# TEST_USB.net
KiCad netlist of a schematic drawn in Altium Designer
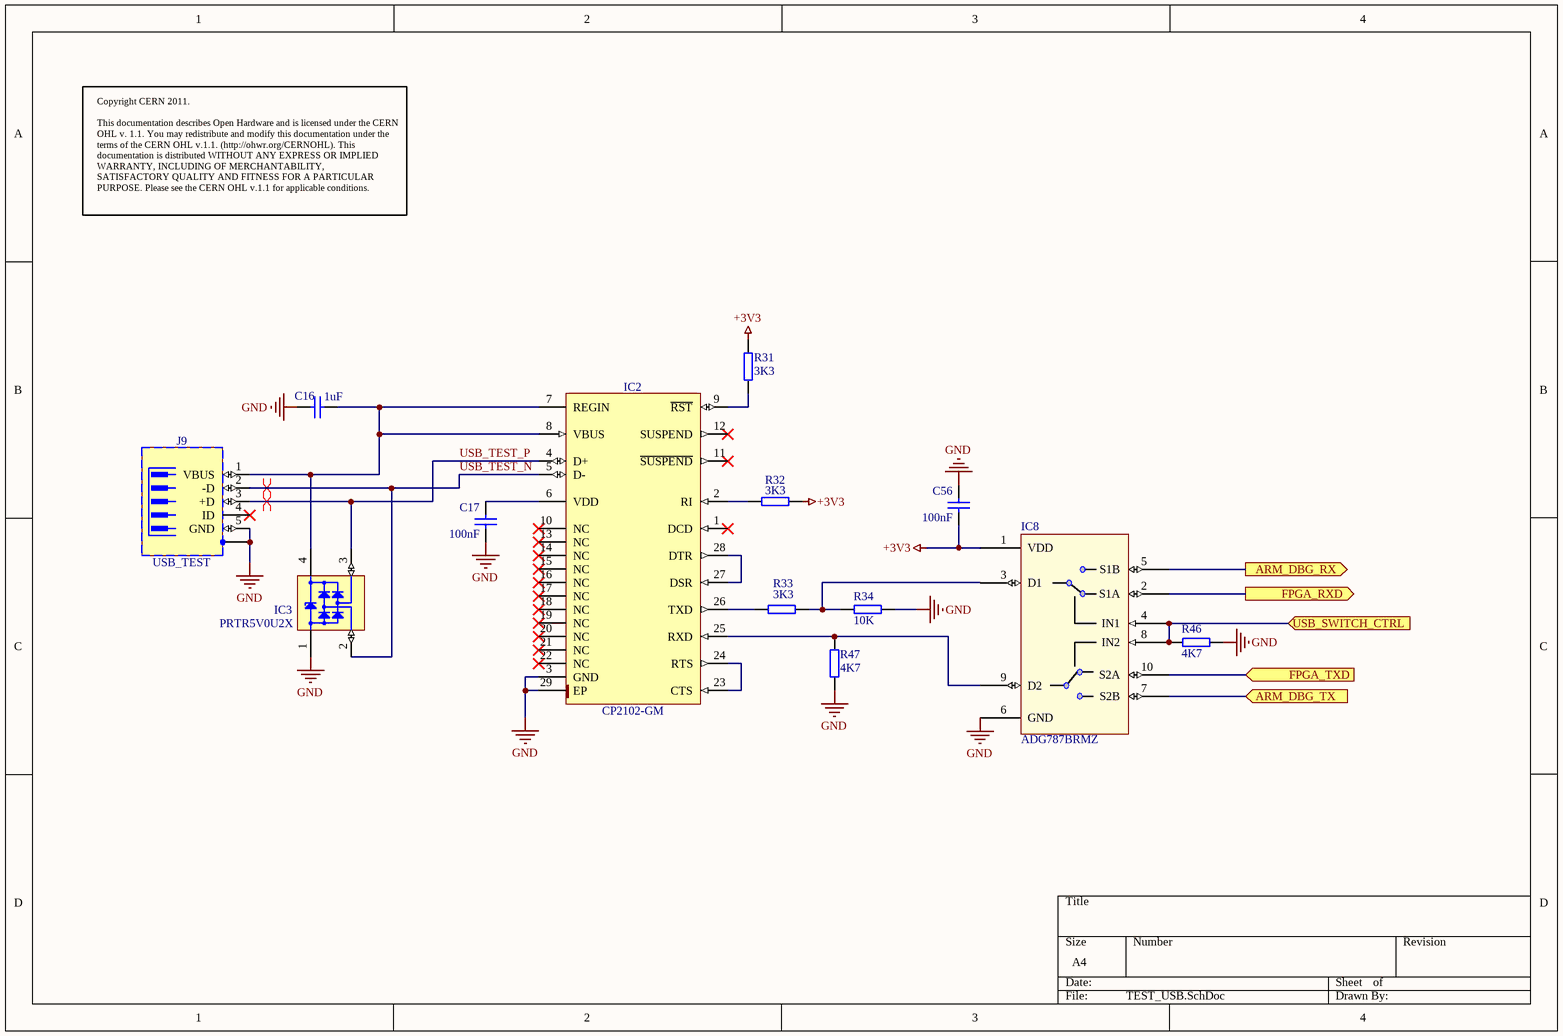
[diagram p0: TEST_USB.SchDoc]

(export (version "E")
  (design (tool "Eeschema 10.0.6"))
  (components
    (comp (ref "C16")
      (value "1uF")
      (footprint "CC1608-0603")
      (description "Capacitor")
      (fields
        (field (name "TOLERANCE") "±10%")
        (field (name "VOLTAGE") "25V")
        (field (name "PUBLISHER") "Altium Limited")
      )
      (libsource (lib "wr_switch") (part "Cap"))
    )
    (comp (ref "C17")
      (value "100nF")
      (footprint "CC1608-0603")
      (description "Capacitor")
      (fields
        (field (name "TOLERANCE") "±10%")
        (field (name "VOLTAGE") "16V")
        (field (name "PUBLISHER") "Altium Limited")
      )
      (libsource (lib "wr_switch") (part "Cap"))
    )
    (comp (ref "C56")
      (value "100nF")
      (footprint "CC1608-0603")
      (description "Capacitor")
      (fields
        (field (name "TOLERANCE") "±10%")
        (field (name "VOLTAGE") "16V")
        (field (name "PUBLISHER") "Altium Limited")
      )
      (libsource (lib "wr_switch") (part "Cap"))
    )
    (comp (ref "IC2")
      (value "CP2102-GM")
      (footprint "7S_WR:QFN50P500X500X100-29N-S335")
      (description "Single-Chip USB to UART Bridge")
      (fields (field (name "MANUFACTURER") "SILICON LABS") (field (name "AUTHOR") "CERN DEM JLC"))
      (libsource (lib "wr_switch") (part "CP2102-GM"))
    )
    (comp (ref "IC3")
      (value "PRTR5V0U2X")
      (footprint "7S_WR:SOT190P230X110-4N")
      (description "Ultra Low Capacitance Double Rail-to-Rail ESD Protection Diode")
      (fields
        (field (name "VOLTAGE") "5.5V")
        (field (name "MANUFACTURER") "PHILIPS NXP")
        (field (name "AUTHOR") "CERN DEM JLC")
      )
      (libsource (lib "wr_switch") (part "PRTR5V0U2X"))
    )
    (comp (ref "IC8")
      (value "ADG787BRMZ")
      (footprint "SOP50P490X109-10N")
      (description "Dual 2:1 MUX/DEMUX USB1.1 Switch")
      (libsource (lib "wr_switch") (part "ADG787BRMZ"))
    )
    (comp (ref "J9")
      (value "USB_TEST")
      (footprint "7S_WR:TYCO_1734035-1")
      (description "5 Pin + 1 Shield Mini USB Type B Receptacle")
      (fields
        (field (name "PART NUMBER") "TYCO_1734035-1")
        (field (name "MANUFACTURER") "TYCO ELECTRONICS")
        (field (name "AUTHOR") "CERN DEM JLC")
      )
      (libsource (lib "wr_switch") (part "TYCO_1734035-1"))
    )
    (comp (ref "R31")
      (value "3K3")
      (footprint "0603")
      (description "SMD Resistor")
      (fields (field (name "TOLERANCE") "±1%"))
      (libsource (lib "wr_switch") (part "RES_SMD"))
    )
    (comp (ref "R32")
      (value "3K3")
      (footprint "0603")
      (description "SMD Resistor")
      (fields (field (name "TOLERANCE") "±1%"))
      (libsource (lib "wr_switch") (part "RES_SMD"))
    )
    (comp (ref "R33")
      (value "3K3")
      (footprint "0603")
      (description "SMD Resistor")
      (fields (field (name "TOLERANCE") "±1%"))
      (libsource (lib "wr_switch") (part "RES_SMD"))
    )
    (comp (ref "R34")
      (value "10K")
      (footprint "0603")
      (description "SMD Resistor")
      (fields (field (name "TOLERANCE") "±1%"))
      (libsource (lib "wr_switch") (part "RES_SMD"))
    )
    (comp (ref "R46")
      (value "4K7")
      (footprint "0603")
      (description "SMD Resistor")
      (fields (field (name "TOLERANCE") "±1%"))
      (libsource (lib "wr_switch") (part "RES_SMD"))
    )
    (comp (ref "R47")
      (value "4K7")
      (footprint "0603")
      (description "SMD Resistor")
      (fields (field (name "TOLERANCE") "±1%"))
      (libsource (lib "wr_switch") (part "RES_SMD"))
    )
  )
  (nets
    (net (code "1") (name "+3V3") (class "Default")
      (node (ref "C56") (pin "2") (pinfunction "2_2") (pintype "passive"))
      (node (ref "IC8") (pin "1") (pinfunction "VDD_1") (pintype "power_in"))
      (node (ref "R31") (pin "2") (pinfunction "2_2") (pintype "passive"))
      (node (ref "R32") (pin "2") (pinfunction "2_2") (pintype "passive"))
    )
    (net (code "2") (name "/ARM_DBG_RX") (class "Default")
      (node (ref "IC8") (pin "5") (pinfunction "S1B_5") (pintype "bidirectional"))
    )
    (net (code "3") (name "/ARM_DBG_TX") (class "Default")
      (node (ref "IC8") (pin "7") (pinfunction "S2B_7") (pintype "bidirectional"))
    )
    (net (code "4") (name "/FPGA_RXD") (class "Default")
      (node (ref "IC8") (pin "2") (pinfunction "S1A_2") (pintype "bidirectional"))
    )
    (net (code "5") (name "/FPGA_TXD") (class "Default")
      (node (ref "IC8") (pin "10") (pinfunction "S2A_10") (pintype "bidirectional"))
    )
    (net (code "6") (name "/USB_SWITCH_CTRL") (class "Default")
      (node (ref "IC8") (pin "4") (pinfunction "IN1_4") (pintype "input"))
      (node (ref "IC8") (pin "8") (pinfunction "IN2_8") (pintype "input"))
      (node (ref "R46") (pin "2") (pinfunction "2_2") (pintype "passive"))
    )
    (net (code "7") (name "/USB_TEST_N") (class "Default")
      (node (ref "IC2") (pin "5") (pinfunction "D-_5") (pintype "bidirectional"))
      (node (ref "IC3") (pin "2") (pinfunction "I/O1_2") (pintype "bidirectional"))
      (node (ref "J9") (pin "2") (pinfunction "-D_2") (pintype "bidirectional"))
    )
    (net (code "8") (name "/USB_TEST_P") (class "Default")
      (node (ref "IC2") (pin "4") (pinfunction "D+_4") (pintype "bidirectional"))
      (node (ref "IC3") (pin "3") (pinfunction "I/O2_3") (pintype "bidirectional"))
      (node (ref "J9") (pin "3") (pinfunction "+D_3") (pintype "bidirectional"))
    )
    (net (code "9") (name "GND") (class "Default")
      (node (ref "C16") (pin "1") (pinfunction "1_1") (pintype "passive"))
      (node (ref "C17") (pin "2") (pinfunction "2_2") (pintype "passive"))
      (node (ref "C56") (pin "1") (pinfunction "1_1") (pintype "passive"))
      (node (ref "IC2") (pin "29") (pinfunction "EP_29") (pintype "power_in"))
      (node (ref "IC2") (pin "3") (pinfunction "GND_3") (pintype "power_in"))
      (node (ref "IC3") (pin "1") (pinfunction "GND_1") (pintype "power_in"))
      (node (ref "IC8") (pin "6") (pinfunction "GND_6") (pintype "power_in"))
      (node (ref "J9") (pin "5") (pinfunction "GND_5") (pintype "bidirectional"))
      (node (ref "J9") (pin "6") (pinfunction "SH_6") (pintype "power_in"))
      (node (ref "R34") (pin "1") (pinfunction "1_1") (pintype "passive"))
      (node (ref "R46") (pin "1") (pinfunction "1_1") (pintype "passive"))
      (node (ref "R47") (pin "2") (pinfunction "2_2") (pintype "passive"))
    )
    (net (code "10") (name "Net-(IC2-CTS)") (class "Default")
      (node (ref "IC2") (pin "23") (pinfunction "CTS_23") (pintype "input"))
      (node (ref "IC2") (pin "24") (pinfunction "RTS_24") (pintype "output"))
    )
    (net (code "11") (name "Net-(IC2-DSR)") (class "Default")
      (node (ref "IC2") (pin "27") (pinfunction "DSR_27") (pintype "input"))
      (node (ref "IC2") (pin "28") (pinfunction "DTR_28") (pintype "output"))
    )
    (net (code "12") (name "Net-(IC2-REGIN)") (class "Default")
      (node (ref "C16") (pin "2") (pinfunction "2_2") (pintype "passive"))
      (node (ref "IC2") (pin "7") (pinfunction "REGIN_7") (pintype "power_in"))
      (node (ref "IC2") (pin "8") (pinfunction "VBUS_8") (pintype "input"))
      (node (ref "IC3") (pin "4") (pinfunction "VCC_4") (pintype "power_in"))
      (node (ref "J9") (pin "1") (pinfunction "VBUS_1") (pintype "bidirectional"))
    )
    (net (code "13") (name "Net-(IC2-RI)") (class "Default")
      (node (ref "IC2") (pin "2") (pinfunction "RI_2") (pintype "input"))
      (node (ref "R32") (pin "1") (pinfunction "1_1") (pintype "passive"))
    )
    (net (code "14") (name "Net-(IC2-RXD)") (class "Default")
      (node (ref "IC2") (pin "25") (pinfunction "RXD_25") (pintype "input"))
      (node (ref "IC8") (pin "9") (pinfunction "D2_9") (pintype "bidirectional"))
      (node (ref "R47") (pin "1") (pinfunction "1_1") (pintype "passive"))
    )
    (net (code "15") (name "Net-(IC2-TXD)") (class "Default")
      (node (ref "IC2") (pin "26") (pinfunction "TXD_26") (pintype "output"))
      (node (ref "R33") (pin "1") (pinfunction "1_1") (pintype "passive"))
    )
    (net (code "16") (name "Net-(IC2-VDD)") (class "Default")
      (node (ref "C17") (pin "1") (pinfunction "1_1") (pintype "passive"))
      (node (ref "IC2") (pin "6") (pinfunction "VDD_6") (pintype "power_in"))
    )
    (net (code "17") (name "Net-(IC2-~{RST})") (class "Default")
      (node (ref "IC2") (pin "9") (pinfunction "~{RST}_9") (pintype "bidirectional"))
      (node (ref "R31") (pin "1") (pinfunction "1_1") (pintype "passive"))
    )
    (net (code "18") (name "Net-(IC8-D1)") (class "Default")
      (node (ref "IC8") (pin "3") (pinfunction "D1_3") (pintype "bidirectional"))
      (node (ref "R33") (pin "2") (pinfunction "2_2") (pintype "passive"))
      (node (ref "R34") (pin "2") (pinfunction "2_2") (pintype "passive"))
    )
    (net (code "19") (name "unconnected-(IC2-DCD-Pad1)") (class "Default")
      (node (ref "IC2") (pin "1") (pinfunction "DCD_1") (pintype "input+no_connect"))
    )
    (net (code "20") (name "unconnected-(IC2-NC-Pad10)") (class "Default")
      (node (ref "IC2") (pin "10") (pinfunction "NC_10") (pintype "passive+no_connect"))
    )
    (net (code "21") (name "unconnected-(IC2-NC-Pad13)") (class "Default")
      (node (ref "IC2") (pin "13") (pinfunction "NC_13") (pintype "passive+no_connect"))
    )
    (net (code "22") (name "unconnected-(IC2-NC-Pad14)") (class "Default")
      (node (ref "IC2") (pin "14") (pinfunction "NC_14") (pintype "passive+no_connect"))
    )
    (net (code "23") (name "unconnected-(IC2-NC-Pad15)") (class "Default")
      (node (ref "IC2") (pin "15") (pinfunction "NC_15") (pintype "passive+no_connect"))
    )
    (net (code "24") (name "unconnected-(IC2-NC-Pad16)") (class "Default")
      (node (ref "IC2") (pin "16") (pinfunction "NC_16") (pintype "passive+no_connect"))
    )
    (net (code "25") (name "unconnected-(IC2-NC-Pad17)") (class "Default")
      (node (ref "IC2") (pin "17") (pinfunction "NC_17") (pintype "passive+no_connect"))
    )
    (net (code "26") (name "unconnected-(IC2-NC-Pad18)") (class "Default")
      (node (ref "IC2") (pin "18") (pinfunction "NC_18") (pintype "passive+no_connect"))
    )
    (net (code "27") (name "unconnected-(IC2-NC-Pad19)") (class "Default")
      (node (ref "IC2") (pin "19") (pinfunction "NC_19") (pintype "passive+no_connect"))
    )
    (net (code "28") (name "unconnected-(IC2-NC-Pad20)") (class "Default")
      (node (ref "IC2") (pin "20") (pinfunction "NC_20") (pintype "passive+no_connect"))
    )
    (net (code "29") (name "unconnected-(IC2-NC-Pad21)") (class "Default")
      (node (ref "IC2") (pin "21") (pinfunction "NC_21") (pintype "passive+no_connect"))
    )
    (net (code "30") (name "unconnected-(IC2-NC-Pad22)") (class "Default")
      (node (ref "IC2") (pin "22") (pinfunction "NC_22") (pintype "passive+no_connect"))
    )
    (net (code "31") (name "unconnected-(IC2-SUSPEND-Pad12)") (class "Default")
      (node (ref "IC2") (pin "12") (pinfunction "SUSPEND_12") (pintype "output+no_connect"))
    )
    (net (code "32") (name "unconnected-(IC2-~{SUSPEND}-Pad11)") (class "Default")
      (node (ref "IC2") (pin "11") (pinfunction "~{SUSPEND}_11") (pintype "output+no_connect"))
    )
    (net (code "33") (name "unconnected-(J9-ID-Pad4)") (class "Default")
      (node (ref "J9") (pin "4") (pinfunction "ID_4") (pintype "passive+no_connect"))
    )
  )
)
